# Button.net
KiCad netlist of a schematic drawn in Altium Designer
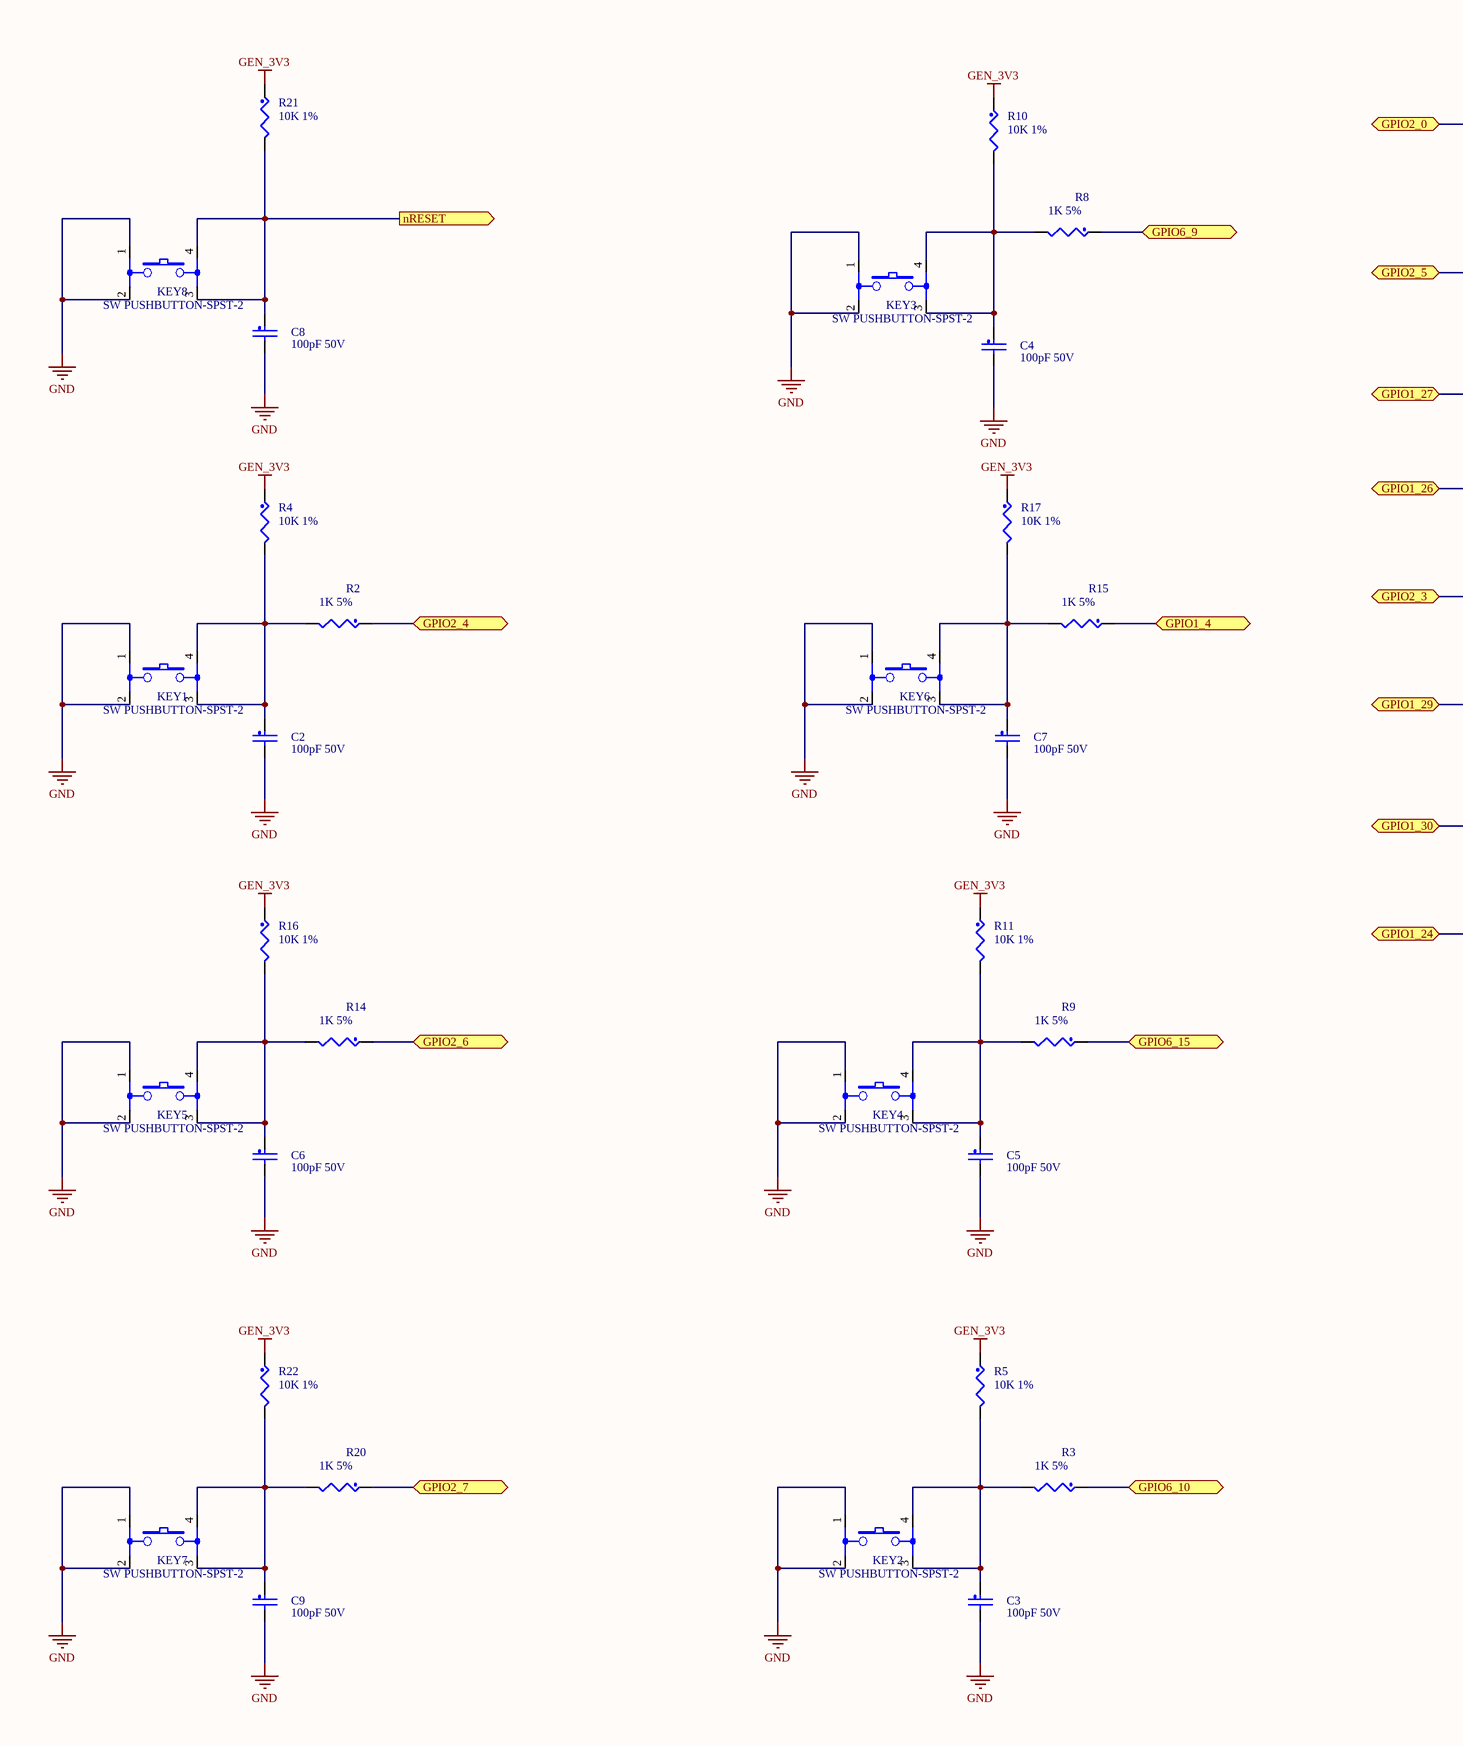
[diagram p0: Button.SchDoc, left]
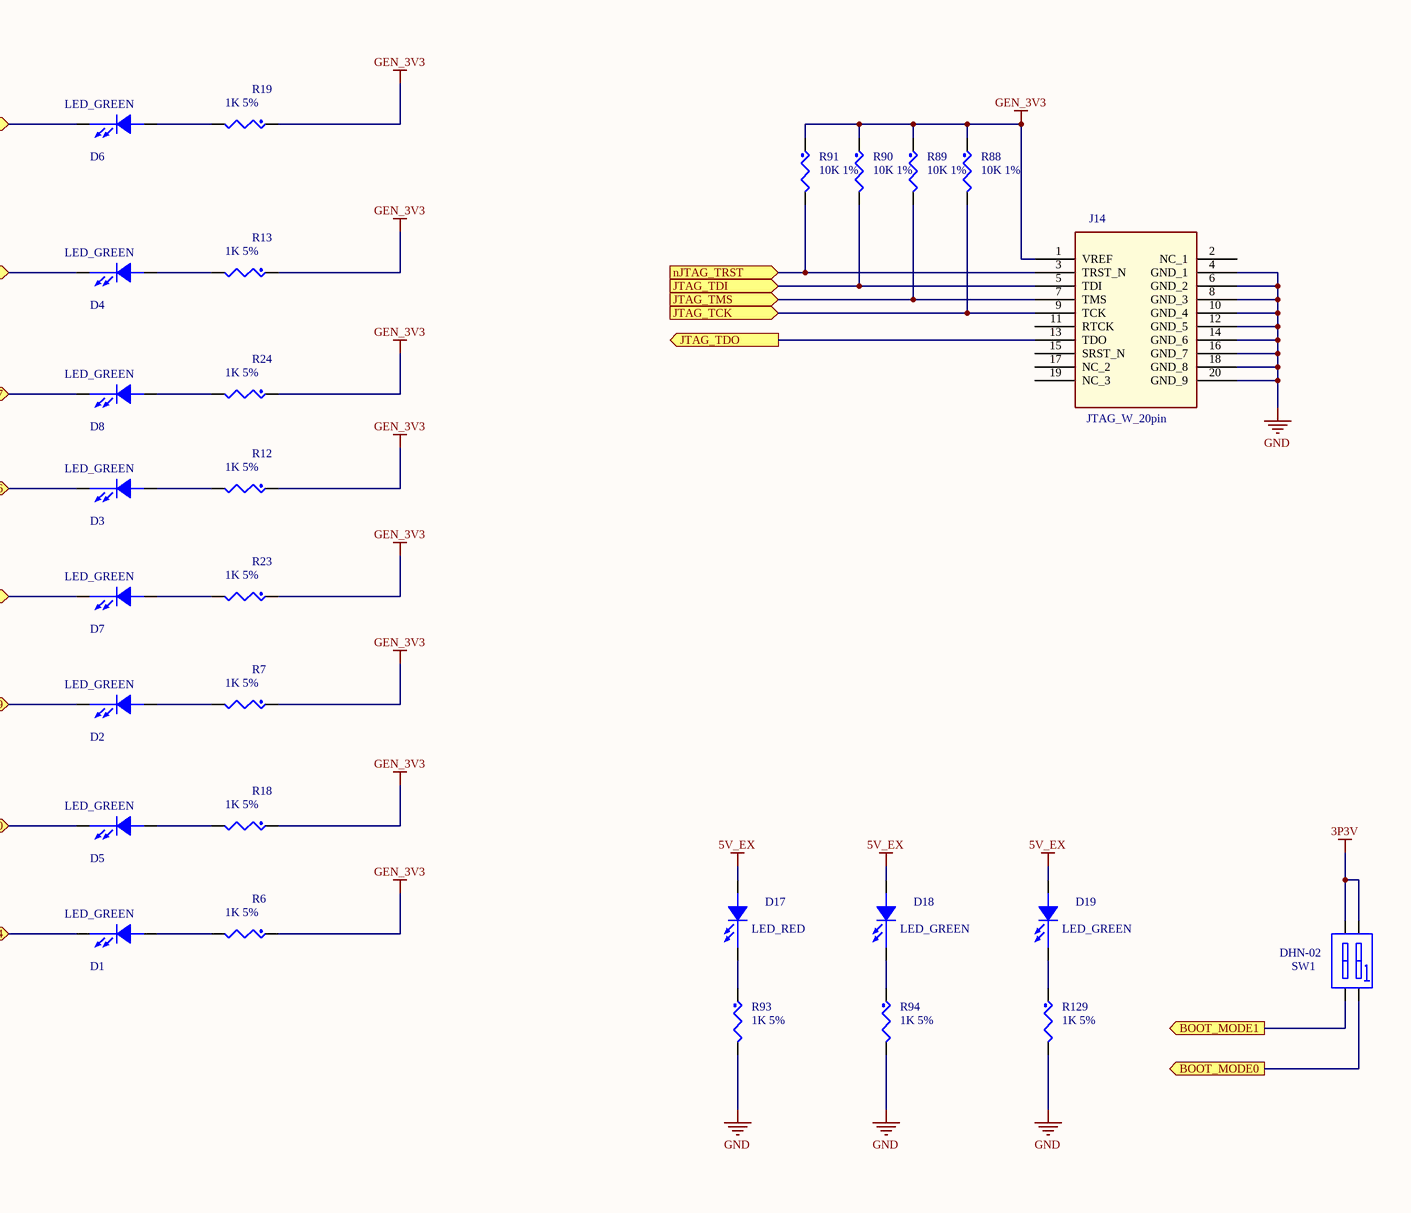
[diagram p1: Button.SchDoc, right]

(export (version "E")
  (design (tool "Eeschema 10.0.6"))
  (components
    (comp (ref "C2")
      (value "100pF 50V")
      (footprint "SC0603")
      (libsource (lib "MY-I.MX6-SCH_Library") (part "CAP_NP"))
    )
    (comp (ref "C3")
      (value "100pF 50V")
      (footprint "SC0603")
      (libsource (lib "MY-I.MX6-SCH_Library") (part "CAP_NP"))
    )
    (comp (ref "C4")
      (value "100pF 50V")
      (footprint "SC0603")
      (libsource (lib "MY-I.MX6-SCH_Library") (part "CAP_NP"))
    )
    (comp (ref "C5")
      (value "100pF 50V")
      (footprint "SC0603")
      (libsource (lib "MY-I.MX6-SCH_Library") (part "CAP_NP"))
    )
    (comp (ref "C6")
      (value "100pF 50V")
      (footprint "SC0603")
      (libsource (lib "MY-I.MX6-SCH_Library") (part "CAP_NP"))
    )
    (comp (ref "C7")
      (value "100pF 50V")
      (footprint "SC0603")
      (libsource (lib "MY-I.MX6-SCH_Library") (part "CAP_NP"))
    )
    (comp (ref "C8")
      (value "100pF 50V")
      (footprint "SC0603")
      (libsource (lib "MY-I.MX6-SCH_Library") (part "CAP_NP"))
    )
    (comp (ref "C9")
      (value "100pF 50V")
      (footprint "SC0603")
      (libsource (lib "MY-I.MX6-SCH_Library") (part "CAP_NP"))
    )
    (comp (ref "D1")
      (value "LED_GREEN")
      (footprint "SD0603")
      (libsource (lib "MY-I.MX6-SCH_Library") (part "LED"))
    )
    (comp (ref "D2")
      (value "LED_GREEN")
      (footprint "SD0603")
      (libsource (lib "MY-I.MX6-SCH_Library") (part "LED"))
    )
    (comp (ref "D3")
      (value "LED_GREEN")
      (footprint "SD0603")
      (libsource (lib "MY-I.MX6-SCH_Library") (part "LED"))
    )
    (comp (ref "D4")
      (value "LED_GREEN")
      (footprint "SD0603")
      (libsource (lib "MY-I.MX6-SCH_Library") (part "LED"))
    )
    (comp (ref "D5")
      (value "LED_GREEN")
      (footprint "SD0603")
      (libsource (lib "MY-I.MX6-SCH_Library") (part "LED"))
    )
    (comp (ref "D6")
      (value "LED_GREEN")
      (footprint "SD0603")
      (libsource (lib "MY-I.MX6-SCH_Library") (part "LED"))
    )
    (comp (ref "D7")
      (value "LED_GREEN")
      (footprint "SD0603")
      (libsource (lib "MY-I.MX6-SCH_Library") (part "LED"))
    )
    (comp (ref "D8")
      (value "LED_GREEN")
      (footprint "SD0603")
      (libsource (lib "MY-I.MX6-SCH_Library") (part "LED"))
    )
    (comp (ref "D17")
      (value "LED_RED")
      (footprint "SD0603")
      (libsource (lib "MY-I.MX6-SCH_Library") (part "LED"))
    )
    (comp (ref "D18")
      (value "LED_GREEN")
      (footprint "SD0603")
      (libsource (lib "MY-I.MX6-SCH_Library") (part "LED"))
    )
    (comp (ref "D19")
      (value "LED_GREEN")
      (footprint "SD0603")
      (libsource (lib "MY-I.MX6-SCH_Library") (part "LED"))
    )
    (comp (ref "J14")
      (value "JTAG_W_20pin")
      (footprint "DIPMH-2-2P54X2P54-20-8-W")
      (libsource (lib "MY-I.MX6-SCH_Library") (part "JTAG_20pin"))
    )
    (comp (ref "KEY1")
      (value "SW PUSHBUTTON-SPST-2")
      (footprint "SB4-6X6-5-1")
      (libsource (lib "MY-I.MX6-SCH_Library") (part "SW PUSHBUTTON-SPST-2"))
    )
    (comp (ref "KEY2")
      (value "SW PUSHBUTTON-SPST-2")
      (footprint "SB4-6X6-5-1")
      (libsource (lib "MY-I.MX6-SCH_Library") (part "SW PUSHBUTTON-SPST-2"))
    )
    (comp (ref "KEY3")
      (value "SW PUSHBUTTON-SPST-2")
      (footprint "SB4-6X6-5-1")
      (libsource (lib "MY-I.MX6-SCH_Library") (part "SW PUSHBUTTON-SPST-2"))
    )
    (comp (ref "KEY4")
      (value "SW PUSHBUTTON-SPST-2")
      (footprint "SB4-6X6-5-1")
      (libsource (lib "MY-I.MX6-SCH_Library") (part "SW PUSHBUTTON-SPST-2"))
    )
    (comp (ref "KEY5")
      (value "SW PUSHBUTTON-SPST-2")
      (footprint "SB4-6X6-5-1")
      (libsource (lib "MY-I.MX6-SCH_Library") (part "SW PUSHBUTTON-SPST-2"))
    )
    (comp (ref "KEY6")
      (value "SW PUSHBUTTON-SPST-2")
      (footprint "SB4-6X6-5-1")
      (libsource (lib "MY-I.MX6-SCH_Library") (part "SW PUSHBUTTON-SPST-2"))
    )
    (comp (ref "KEY7")
      (value "SW PUSHBUTTON-SPST-2")
      (footprint "SB4-6X6-5-1")
      (libsource (lib "MY-I.MX6-SCH_Library") (part "SW PUSHBUTTON-SPST-2"))
    )
    (comp (ref "KEY8")
      (value "SW PUSHBUTTON-SPST-2")
      (footprint "SB4-6X6-5-1")
      (libsource (lib "MY-I.MX6-SCH_Library") (part "SW PUSHBUTTON-SPST-2"))
    )
    (comp (ref "R2")
      (value "1K 5%")
      (footprint "SR0603")
      (libsource (lib "MY-I.MX6-SCH_Library") (part "RES"))
    )
    (comp (ref "R3")
      (value "1K 5%")
      (footprint "SR0603")
      (libsource (lib "MY-I.MX6-SCH_Library") (part "RES"))
    )
    (comp (ref "R4")
      (value "10K 1%")
      (footprint "SR0603")
      (libsource (lib "MY-I.MX6-SCH_Library") (part "RES"))
    )
    (comp (ref "R5")
      (value "10K 1%")
      (footprint "SR0603")
      (libsource (lib "MY-I.MX6-SCH_Library") (part "RES"))
    )
    (comp (ref "R6")
      (value "1K 5%")
      (footprint "SR0603")
      (libsource (lib "MY-I.MX6-SCH_Library") (part "RES"))
    )
    (comp (ref "R7")
      (value "1K 5%")
      (footprint "SR0603")
      (libsource (lib "MY-I.MX6-SCH_Library") (part "RES"))
    )
    (comp (ref "R8")
      (value "1K 5%")
      (footprint "SR0603")
      (libsource (lib "MY-I.MX6-SCH_Library") (part "RES"))
    )
    (comp (ref "R9")
      (value "1K 5%")
      (footprint "SR0603")
      (libsource (lib "MY-I.MX6-SCH_Library") (part "RES"))
    )
    (comp (ref "R10")
      (value "10K 1%")
      (footprint "SR0603")
      (libsource (lib "MY-I.MX6-SCH_Library") (part "RES"))
    )
    (comp (ref "R11")
      (value "10K 1%")
      (footprint "SR0603")
      (libsource (lib "MY-I.MX6-SCH_Library") (part "RES"))
    )
    (comp (ref "R12")
      (value "1K 5%")
      (footprint "SR0603")
      (libsource (lib "MY-I.MX6-SCH_Library") (part "RES"))
    )
    (comp (ref "R13")
      (value "1K 5%")
      (footprint "SR0603")
      (libsource (lib "MY-I.MX6-SCH_Library") (part "RES"))
    )
    (comp (ref "R14")
      (value "1K 5%")
      (footprint "SR0603")
      (libsource (lib "MY-I.MX6-SCH_Library") (part "RES"))
    )
    (comp (ref "R15")
      (value "1K 5%")
      (footprint "SR0603")
      (libsource (lib "MY-I.MX6-SCH_Library") (part "RES"))
    )
    (comp (ref "R16")
      (value "10K 1%")
      (footprint "SR0603")
      (libsource (lib "MY-I.MX6-SCH_Library") (part "RES"))
    )
    (comp (ref "R17")
      (value "10K 1%")
      (footprint "SR0603")
      (libsource (lib "MY-I.MX6-SCH_Library") (part "RES"))
    )
    (comp (ref "R18")
      (value "1K 5%")
      (footprint "SR0603")
      (libsource (lib "MY-I.MX6-SCH_Library") (part "RES"))
    )
    (comp (ref "R19")
      (value "1K 5%")
      (footprint "SR0603")
      (libsource (lib "MY-I.MX6-SCH_Library") (part "RES"))
    )
    (comp (ref "R20")
      (value "1K 5%")
      (footprint "SR0603")
      (libsource (lib "MY-I.MX6-SCH_Library") (part "RES"))
    )
    (comp (ref "R21")
      (value "10K 1%")
      (footprint "SR0603")
      (libsource (lib "MY-I.MX6-SCH_Library") (part "RES"))
    )
    (comp (ref "R22")
      (value "10K 1%")
      (footprint "SR0603")
      (libsource (lib "MY-I.MX6-SCH_Library") (part "RES"))
    )
    (comp (ref "R23")
      (value "1K 5%")
      (footprint "SR0603")
      (libsource (lib "MY-I.MX6-SCH_Library") (part "RES"))
    )
    (comp (ref "R24")
      (value "1K 5%")
      (footprint "SR0603")
      (libsource (lib "MY-I.MX6-SCH_Library") (part "RES"))
    )
    (comp (ref "R88")
      (value "10K 1%")
      (footprint "SR0603")
      (libsource (lib "MY-I.MX6-SCH_Library") (part "RES"))
    )
    (comp (ref "R89")
      (value "10K 1%")
      (footprint "SR0603")
      (libsource (lib "MY-I.MX6-SCH_Library") (part "RES"))
    )
    (comp (ref "R90")
      (value "10K 1%")
      (footprint "SR0603")
      (libsource (lib "MY-I.MX6-SCH_Library") (part "RES"))
    )
    (comp (ref "R91")
      (value "10K 1%")
      (footprint "SR0603")
      (libsource (lib "MY-I.MX6-SCH_Library") (part "RES"))
    )
    (comp (ref "R93")
      (value "1K 5%")
      (footprint "SR0603")
      (libsource (lib "MY-I.MX6-SCH_Library") (part "RES"))
    )
    (comp (ref "R94")
      (value "1K 5%")
      (footprint "SR0603")
      (libsource (lib "MY-I.MX6-SCH_Library") (part "RES"))
    )
    (comp (ref "R129")
      (value "1K 5%")
      (footprint "SR0603")
      (libsource (lib "MY-I.MX6-SCH_Library") (part "RES"))
    )
    (comp (ref "SW1")
      (value "DHN-02")
      (footprint "SW4-10X4-2-1")
      (libsource (lib "MY-I.MX6-SCH_Library") (part "SW DIP-2_0"))
    )
  )
  (nets
    (net (code "1") (name "/BOOT_MODE0") (class "Default")
      (node (ref "SW1") (pin "4") (pinfunction "B1_4") (pintype "passive"))
    )
    (net (code "2") (name "/BOOT_MODE1") (class "Default")
      (node (ref "SW1") (pin "3") (pinfunction "B2_3") (pintype "passive"))
    )
    (net (code "3") (name "/GPIO1_4") (class "Default")
      (node (ref "R15") (pin "1") (pinfunction "1_1") (pintype "passive"))
    )
    (net (code "4") (name "/GPIO1_24") (class "Default")
      (node (ref "D1") (pin "2") (pinfunction "CATHODE_2") (pintype "passive"))
    )
    (net (code "5") (name "/GPIO1_26") (class "Default")
      (node (ref "D3") (pin "2") (pinfunction "CATHODE_2") (pintype "passive"))
    )
    (net (code "6") (name "/GPIO1_27") (class "Default")
      (node (ref "D8") (pin "2") (pinfunction "CATHODE_2") (pintype "passive"))
    )
    (net (code "7") (name "/GPIO1_29") (class "Default")
      (node (ref "D2") (pin "2") (pinfunction "CATHODE_2") (pintype "passive"))
    )
    (net (code "8") (name "/GPIO1_30") (class "Default")
      (node (ref "D5") (pin "2") (pinfunction "CATHODE_2") (pintype "passive"))
    )
    (net (code "9") (name "/GPIO2_0") (class "Default")
      (node (ref "D6") (pin "2") (pinfunction "CATHODE_2") (pintype "passive"))
    )
    (net (code "10") (name "/GPIO2_3") (class "Default")
      (node (ref "D7") (pin "2") (pinfunction "CATHODE_2") (pintype "passive"))
    )
    (net (code "11") (name "/GPIO2_4") (class "Default")
      (node (ref "R2") (pin "1") (pinfunction "1_1") (pintype "passive"))
    )
    (net (code "12") (name "/GPIO2_5") (class "Default")
      (node (ref "D4") (pin "2") (pinfunction "CATHODE_2") (pintype "passive"))
    )
    (net (code "13") (name "/GPIO2_6") (class "Default")
      (node (ref "R14") (pin "1") (pinfunction "1_1") (pintype "passive"))
    )
    (net (code "14") (name "/GPIO2_7") (class "Default")
      (node (ref "R20") (pin "1") (pinfunction "1_1") (pintype "passive"))
    )
    (net (code "15") (name "/GPIO6_9") (class "Default")
      (node (ref "R8") (pin "1") (pinfunction "1_1") (pintype "passive"))
    )
    (net (code "16") (name "/GPIO6_10") (class "Default")
      (node (ref "R3") (pin "1") (pinfunction "1_1") (pintype "passive"))
    )
    (net (code "17") (name "/GPIO6_15") (class "Default")
      (node (ref "R9") (pin "1") (pinfunction "1_1") (pintype "passive"))
    )
    (net (code "18") (name "/JTAG_TCK") (class "Default")
      (node (ref "J14") (pin "9") (pinfunction "TCK_9") (pintype "passive"))
      (node (ref "R88") (pin "2") (pinfunction "2_2") (pintype "passive"))
    )
    (net (code "19") (name "/JTAG_TDI") (class "Default")
      (node (ref "J14") (pin "5") (pinfunction "TDI_5") (pintype "passive"))
      (node (ref "R90") (pin "2") (pinfunction "2_2") (pintype "passive"))
    )
    (net (code "20") (name "/JTAG_TDO") (class "Default")
      (node (ref "J14") (pin "13") (pinfunction "TDO_13") (pintype "passive"))
    )
    (net (code "21") (name "/JTAG_TMS") (class "Default")
      (node (ref "J14") (pin "7") (pinfunction "TMS_7") (pintype "passive"))
      (node (ref "R89") (pin "2") (pinfunction "2_2") (pintype "passive"))
    )
    (net (code "22") (name "/nJTAG_TRST") (class "Default")
      (node (ref "J14") (pin "3") (pinfunction "TRST_N_3") (pintype "passive"))
      (node (ref "R91") (pin "2") (pinfunction "2_2") (pintype "passive"))
    )
    (net (code "23") (name "/nRESET") (class "Default")
      (node (ref "C8") (pin "1") (pinfunction "1_1") (pintype "passive"))
      (node (ref "KEY8") (pin "3") (pinfunction "3_3") (pintype "passive"))
      (node (ref "KEY8") (pin "4") (pinfunction "4_4") (pintype "passive"))
      (node (ref "R21") (pin "2") (pinfunction "2_2") (pintype "passive"))
    )
    (net (code "24") (name "3P3V") (class "Default")
      (node (ref "SW1") (pin "1") (pinfunction "A1_1") (pintype "passive"))
      (node (ref "SW1") (pin "2") (pinfunction "A2_2") (pintype "passive"))
    )
    (net (code "25") (name "5V_EX") (class "Default")
      (node (ref "D17") (pin "1") (pinfunction "ANODE_1") (pintype "passive"))
      (node (ref "D18") (pin "1") (pinfunction "ANODE_1") (pintype "passive"))
      (node (ref "D19") (pin "1") (pinfunction "ANODE_1") (pintype "passive"))
    )
    (net (code "26") (name "GEN_3V3") (class "Default")
      (node (ref "J14") (pin "1") (pinfunction "VREF_1") (pintype "passive"))
      (node (ref "R10") (pin "1") (pinfunction "1_1") (pintype "passive"))
      (node (ref "R11") (pin "1") (pinfunction "1_1") (pintype "passive"))
      (node (ref "R12") (pin "1") (pinfunction "1_1") (pintype "passive"))
      (node (ref "R13") (pin "1") (pinfunction "1_1") (pintype "passive"))
      (node (ref "R16") (pin "1") (pinfunction "1_1") (pintype "passive"))
      (node (ref "R17") (pin "1") (pinfunction "1_1") (pintype "passive"))
      (node (ref "R18") (pin "1") (pinfunction "1_1") (pintype "passive"))
      (node (ref "R19") (pin "1") (pinfunction "1_1") (pintype "passive"))
      (node (ref "R21") (pin "1") (pinfunction "1_1") (pintype "passive"))
      (node (ref "R22") (pin "1") (pinfunction "1_1") (pintype "passive"))
      (node (ref "R23") (pin "1") (pinfunction "1_1") (pintype "passive"))
      (node (ref "R24") (pin "1") (pinfunction "1_1") (pintype "passive"))
      (node (ref "R4") (pin "1") (pinfunction "1_1") (pintype "passive"))
      (node (ref "R5") (pin "1") (pinfunction "1_1") (pintype "passive"))
      (node (ref "R6") (pin "1") (pinfunction "1_1") (pintype "passive"))
      (node (ref "R7") (pin "1") (pinfunction "1_1") (pintype "passive"))
      (node (ref "R88") (pin "1") (pinfunction "1_1") (pintype "passive"))
      (node (ref "R89") (pin "1") (pinfunction "1_1") (pintype "passive"))
      (node (ref "R90") (pin "1") (pinfunction "1_1") (pintype "passive"))
      (node (ref "R91") (pin "1") (pinfunction "1_1") (pintype "passive"))
    )
    (net (code "27") (name "GND") (class "Default")
      (node (ref "C2") (pin "2") (pinfunction "2_2") (pintype "passive"))
      (node (ref "C3") (pin "2") (pinfunction "2_2") (pintype "passive"))
      (node (ref "C4") (pin "2") (pinfunction "2_2") (pintype "passive"))
      (node (ref "C5") (pin "2") (pinfunction "2_2") (pintype "passive"))
      (node (ref "C6") (pin "2") (pinfunction "2_2") (pintype "passive"))
      (node (ref "C7") (pin "2") (pinfunction "2_2") (pintype "passive"))
      (node (ref "C8") (pin "2") (pinfunction "2_2") (pintype "passive"))
      (node (ref "C9") (pin "2") (pinfunction "2_2") (pintype "passive"))
      (node (ref "J14") (pin "10") (pinfunction "GND_4_10") (pintype "passive"))
      (node (ref "J14") (pin "12") (pinfunction "GND_5_12") (pintype "passive"))
      (node (ref "J14") (pin "14") (pinfunction "GND_6_14") (pintype "passive"))
      (node (ref "J14") (pin "16") (pinfunction "GND_7_16") (pintype "passive"))
      (node (ref "J14") (pin "18") (pinfunction "GND_8_18") (pintype "passive"))
      (node (ref "J14") (pin "20") (pinfunction "GND_9_20") (pintype "passive"))
      (node (ref "J14") (pin "4") (pinfunction "GND_1_4") (pintype "passive"))
      (node (ref "J14") (pin "6") (pinfunction "GND_2_6") (pintype "passive"))
      (node (ref "J14") (pin "8") (pinfunction "GND_3_8") (pintype "passive"))
      (node (ref "KEY1") (pin "1") (pinfunction "1_1") (pintype "passive"))
      (node (ref "KEY1") (pin "2") (pinfunction "2_2") (pintype "passive"))
      (node (ref "KEY2") (pin "1") (pinfunction "1_1") (pintype "passive"))
      (node (ref "KEY2") (pin "2") (pinfunction "2_2") (pintype "passive"))
      (node (ref "KEY3") (pin "1") (pinfunction "1_1") (pintype "passive"))
      (node (ref "KEY3") (pin "2") (pinfunction "2_2") (pintype "passive"))
      (node (ref "KEY4") (pin "1") (pinfunction "1_1") (pintype "passive"))
      (node (ref "KEY4") (pin "2") (pinfunction "2_2") (pintype "passive"))
      (node (ref "KEY5") (pin "1") (pinfunction "1_1") (pintype "passive"))
      (node (ref "KEY5") (pin "2") (pinfunction "2_2") (pintype "passive"))
      (node (ref "KEY6") (pin "1") (pinfunction "1_1") (pintype "passive"))
      (node (ref "KEY6") (pin "2") (pinfunction "2_2") (pintype "passive"))
      (node (ref "KEY7") (pin "1") (pinfunction "1_1") (pintype "passive"))
      (node (ref "KEY7") (pin "2") (pinfunction "2_2") (pintype "passive"))
      (node (ref "KEY8") (pin "1") (pinfunction "1_1") (pintype "passive"))
      (node (ref "KEY8") (pin "2") (pinfunction "2_2") (pintype "passive"))
      (node (ref "R129") (pin "2") (pinfunction "2_2") (pintype "passive"))
      (node (ref "R93") (pin "2") (pinfunction "2_2") (pintype "passive"))
      (node (ref "R94") (pin "2") (pinfunction "2_2") (pintype "passive"))
    )
    (net (code "28") (name "Net-(C2-Pad1)") (class "Default")
      (node (ref "C2") (pin "1") (pinfunction "1_1") (pintype "passive"))
      (node (ref "KEY1") (pin "3") (pinfunction "3_3") (pintype "passive"))
      (node (ref "KEY1") (pin "4") (pinfunction "4_4") (pintype "passive"))
      (node (ref "R2") (pin "2") (pinfunction "2_2") (pintype "passive"))
      (node (ref "R4") (pin "2") (pinfunction "2_2") (pintype "passive"))
    )
    (net (code "29") (name "Net-(C3-Pad1)") (class "Default")
      (node (ref "C3") (pin "1") (pinfunction "1_1") (pintype "passive"))
      (node (ref "KEY2") (pin "3") (pinfunction "3_3") (pintype "passive"))
      (node (ref "KEY2") (pin "4") (pinfunction "4_4") (pintype "passive"))
      (node (ref "R3") (pin "2") (pinfunction "2_2") (pintype "passive"))
      (node (ref "R5") (pin "2") (pinfunction "2_2") (pintype "passive"))
    )
    (net (code "30") (name "Net-(C4-Pad1)") (class "Default")
      (node (ref "C4") (pin "1") (pinfunction "1_1") (pintype "passive"))
      (node (ref "KEY3") (pin "3") (pinfunction "3_3") (pintype "passive"))
      (node (ref "KEY3") (pin "4") (pinfunction "4_4") (pintype "passive"))
      (node (ref "R10") (pin "2") (pinfunction "2_2") (pintype "passive"))
      (node (ref "R8") (pin "2") (pinfunction "2_2") (pintype "passive"))
    )
    (net (code "31") (name "Net-(C5-Pad1)") (class "Default")
      (node (ref "C5") (pin "1") (pinfunction "1_1") (pintype "passive"))
      (node (ref "KEY4") (pin "3") (pinfunction "3_3") (pintype "passive"))
      (node (ref "KEY4") (pin "4") (pinfunction "4_4") (pintype "passive"))
      (node (ref "R11") (pin "2") (pinfunction "2_2") (pintype "passive"))
      (node (ref "R9") (pin "2") (pinfunction "2_2") (pintype "passive"))
    )
    (net (code "32") (name "Net-(C6-Pad1)") (class "Default")
      (node (ref "C6") (pin "1") (pinfunction "1_1") (pintype "passive"))
      (node (ref "KEY5") (pin "3") (pinfunction "3_3") (pintype "passive"))
      (node (ref "KEY5") (pin "4") (pinfunction "4_4") (pintype "passive"))
      (node (ref "R14") (pin "2") (pinfunction "2_2") (pintype "passive"))
      (node (ref "R16") (pin "2") (pinfunction "2_2") (pintype "passive"))
    )
    (net (code "33") (name "Net-(C7-Pad1)") (class "Default")
      (node (ref "C7") (pin "1") (pinfunction "1_1") (pintype "passive"))
      (node (ref "KEY6") (pin "3") (pinfunction "3_3") (pintype "passive"))
      (node (ref "KEY6") (pin "4") (pinfunction "4_4") (pintype "passive"))
      (node (ref "R15") (pin "2") (pinfunction "2_2") (pintype "passive"))
      (node (ref "R17") (pin "2") (pinfunction "2_2") (pintype "passive"))
    )
    (net (code "34") (name "Net-(C9-Pad1)") (class "Default")
      (node (ref "C9") (pin "1") (pinfunction "1_1") (pintype "passive"))
      (node (ref "KEY7") (pin "3") (pinfunction "3_3") (pintype "passive"))
      (node (ref "KEY7") (pin "4") (pinfunction "4_4") (pintype "passive"))
      (node (ref "R20") (pin "2") (pinfunction "2_2") (pintype "passive"))
      (node (ref "R22") (pin "2") (pinfunction "2_2") (pintype "passive"))
    )
    (net (code "35") (name "Net-(D1-ANODE)") (class "Default")
      (node (ref "D1") (pin "1") (pinfunction "ANODE_1") (pintype "passive"))
      (node (ref "R6") (pin "2") (pinfunction "2_2") (pintype "passive"))
    )
    (net (code "36") (name "Net-(D2-ANODE)") (class "Default")
      (node (ref "D2") (pin "1") (pinfunction "ANODE_1") (pintype "passive"))
      (node (ref "R7") (pin "2") (pinfunction "2_2") (pintype "passive"))
    )
    (net (code "37") (name "Net-(D3-ANODE)") (class "Default")
      (node (ref "D3") (pin "1") (pinfunction "ANODE_1") (pintype "passive"))
      (node (ref "R12") (pin "2") (pinfunction "2_2") (pintype "passive"))
    )
    (net (code "38") (name "Net-(D4-ANODE)") (class "Default")
      (node (ref "D4") (pin "1") (pinfunction "ANODE_1") (pintype "passive"))
      (node (ref "R13") (pin "2") (pinfunction "2_2") (pintype "passive"))
    )
    (net (code "39") (name "Net-(D5-ANODE)") (class "Default")
      (node (ref "D5") (pin "1") (pinfunction "ANODE_1") (pintype "passive"))
      (node (ref "R18") (pin "2") (pinfunction "2_2") (pintype "passive"))
    )
    (net (code "40") (name "Net-(D6-ANODE)") (class "Default")
      (node (ref "D6") (pin "1") (pinfunction "ANODE_1") (pintype "passive"))
      (node (ref "R19") (pin "2") (pinfunction "2_2") (pintype "passive"))
    )
    (net (code "41") (name "Net-(D7-ANODE)") (class "Default")
      (node (ref "D7") (pin "1") (pinfunction "ANODE_1") (pintype "passive"))
      (node (ref "R23") (pin "2") (pinfunction "2_2") (pintype "passive"))
    )
    (net (code "42") (name "Net-(D8-ANODE)") (class "Default")
      (node (ref "D8") (pin "1") (pinfunction "ANODE_1") (pintype "passive"))
      (node (ref "R24") (pin "2") (pinfunction "2_2") (pintype "passive"))
    )
    (net (code "43") (name "Net-(D17-CATHODE)") (class "Default")
      (node (ref "D17") (pin "2") (pinfunction "CATHODE_2") (pintype "passive"))
      (node (ref "R93") (pin "1") (pinfunction "1_1") (pintype "passive"))
    )
    (net (code "44") (name "Net-(D18-CATHODE)") (class "Default")
      (node (ref "D18") (pin "2") (pinfunction "CATHODE_2") (pintype "passive"))
      (node (ref "R94") (pin "1") (pinfunction "1_1") (pintype "passive"))
    )
    (net (code "45") (name "Net-(D19-CATHODE)") (class "Default")
      (node (ref "D19") (pin "2") (pinfunction "CATHODE_2") (pintype "passive"))
      (node (ref "R129") (pin "1") (pinfunction "1_1") (pintype "passive"))
    )
    (net (code "46") (name "unconnected-(J14-NC_1-Pad2)") (class "Default")
      (node (ref "J14") (pin "2") (pinfunction "NC_1_2") (pintype "passive"))
    )
    (net (code "47") (name "unconnected-(J14-NC_2-Pad17)") (class "Default")
      (node (ref "J14") (pin "17") (pinfunction "NC_2_17") (pintype "passive"))
    )
    (net (code "48") (name "unconnected-(J14-NC_3-Pad19)") (class "Default")
      (node (ref "J14") (pin "19") (pinfunction "NC_3_19") (pintype "passive"))
    )
    (net (code "49") (name "unconnected-(J14-RTCK-Pad11)") (class "Default")
      (node (ref "J14") (pin "11") (pinfunction "RTCK_11") (pintype "passive"))
    )
    (net (code "50") (name "unconnected-(J14-SRST_N-Pad15)") (class "Default")
      (node (ref "J14") (pin "15") (pinfunction "SRST_N_15") (pintype "passive"))
    )
  )
)
